# ArduSensor-Magnet.net
KiCad netlist of a schematic drawn in EAGLE
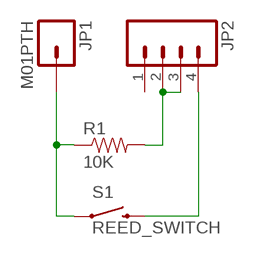
[diagram p0: schematic, sheet 1]

(export (version "E")
  (design (tool "Eeschema 10.0.6"))
  (components
    (comp (ref "JP1")
      (value "M01PTH")
      (footprint "eagle-import:1X01")
      (libsource (lib "eagle-import") (part "M01PTH"))
    )
    (comp (ref "JP2")
      (value "M04PTH")
      (footprint "eagle-import:1X04")
      (libsource (lib "eagle-import") (part "M04PTH"))
    )
    (comp (ref "R1")
      (value "10K")
      (footprint "eagle-import:AXIAL-0.3")
      (libsource (lib "eagle-import") (part "RESISTORAXIAL-0.3"))
    )
    (comp (ref "S1")
      (value "REED_SWITCH")
      (footprint "eagle-import:REED_SWITCH_PLASTIC")
      (libsource (lib "eagle-import") (part "SWITCH-MOMENTARY-2PTH_REED2"))
    )
  )
  (nets
    (net (code "1") (name "Net-(R1-1)") (class "Default")
      (node (ref "JP1") (pin "1") (pinfunction "1_1") (pintype "passive"))
      (node (ref "R1") (pin "P$1") (pinfunction "1_P$1") (pintype "passive"))
      (node (ref "S1") (pin "P$1") (pinfunction "1_P$1") (pintype "passive"))
    )
    (net (code "2") (name "Net-(R1-2)") (class "Default")
      (node (ref "JP2") (pin "2") (pinfunction "2_2") (pintype "passive"))
      (node (ref "JP2") (pin "3") (pinfunction "3_3") (pintype "passive"))
      (node (ref "R1") (pin "P$2") (pinfunction "2_P$2") (pintype "passive"))
    )
    (net (code "3") (name "Net-(S1-2)") (class "Default")
      (node (ref "JP2") (pin "4") (pinfunction "4_4") (pintype "passive"))
      (node (ref "S1") (pin "P$2") (pinfunction "2_P$2") (pintype "passive"))
    )
    (net (code "4") (name "unconnected-(JP2-Pad1)") (class "Default")
      (node (ref "JP2") (pin "1") (pinfunction "1_1") (pintype "passive"))
    )
  )
)
